# ECUv2.net
KiCad netlist of a schematic drawn in Altium Designer
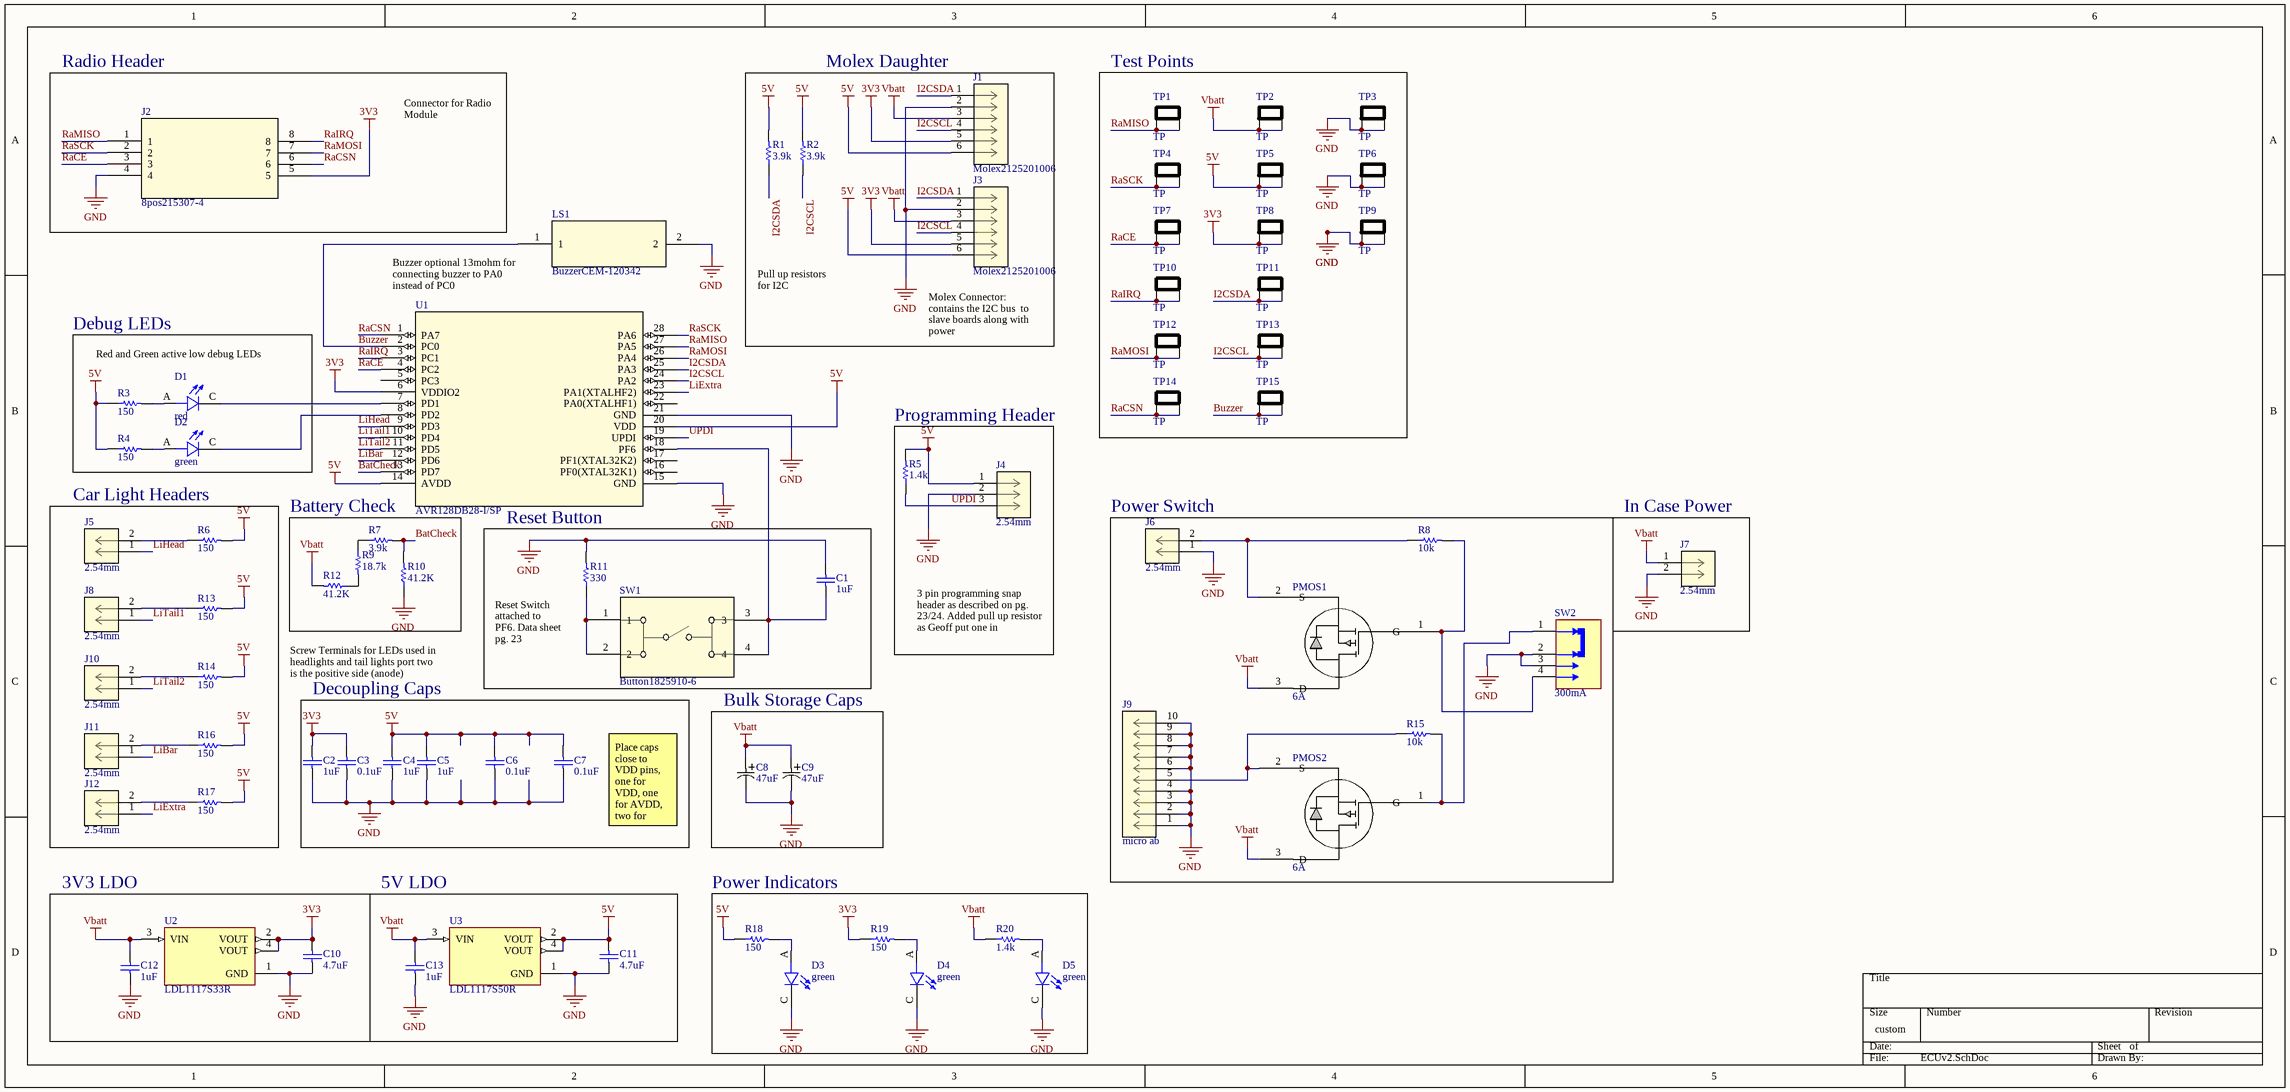
[diagram p0: ECUv2.SchDoc]

(export (version "E")
  (design (tool "Eeschema 10.0.6"))
  (components
    (comp (ref "C1")
      (value "1uF")
      (footprint "RES 0805")
      (fields
        (field (name "MANUFACTURER") "Samsung")
        (field (name "MANUFACTURER PART NUMBER") "CL21B105KBFNNNE")
      )
      (libsource (lib "Schlib1") (part "CAP CER 1uF 10% 50V 0805"))
    )
    (comp (ref "C2")
      (value "1uF")
      (footprint "RES 0805")
      (fields
        (field (name "MANUFACTURER") "Samsung")
        (field (name "MANUFACTURER PART NUMBER") "CL21B105KBFNNNE")
      )
      (libsource (lib "Schlib1") (part "CAP CER 1uF 10% 50V 0805"))
    )
    (comp (ref "C3")
      (value "0.1uF")
      (footprint "RES 0805")
      (fields
        (field (name "MANUFACTURER") "Yageo")
        (field (name "MANUFACTURER PART NUMBER") "CC0805KRX7R9BB104")
      )
      (libsource (lib "Schlib1") (part "CAP CER 0.1uF 10% 50V 0805"))
    )
    (comp (ref "C4")
      (value "1uF")
      (footprint "RES 0805")
      (fields
        (field (name "MANUFACTURER") "Samsung")
        (field (name "MANUFACTURER PART NUMBER") "CL21B105KBFNNNE")
      )
      (libsource (lib "Schlib1") (part "CAP CER 1uF 10% 50V 0805"))
    )
    (comp (ref "C5")
      (value "1uF")
      (footprint "RES 0805")
      (fields
        (field (name "MANUFACTURER") "Samsung")
        (field (name "MANUFACTURER PART NUMBER") "CL21B105KBFNNNE")
      )
      (libsource (lib "Schlib1") (part "CAP CER 1uF 10% 50V 0805"))
    )
    (comp (ref "C6")
      (value "0.1uF")
      (footprint "RES 0805")
      (fields
        (field (name "MANUFACTURER") "Yageo")
        (field (name "MANUFACTURER PART NUMBER") "CC0805KRX7R9BB104")
      )
      (libsource (lib "Schlib1") (part "CAP CER 0.1uF 10% 50V 0805"))
    )
    (comp (ref "C7")
      (value "0.1uF")
      (footprint "RES 0805")
      (fields
        (field (name "MANUFACTURER") "Yageo")
        (field (name "MANUFACTURER PART NUMBER") "CC0805KRX7R9BB104")
      )
      (libsource (lib "Schlib1") (part "CAP CER 0.1uF 10% 50V 0805"))
    )
    (comp (ref "C8")
      (value "47uF")
      (footprint "CAP ELC 47uF")
      (fields
        (field (name "MANUFACTURER") "Nichicon")
        (field (name "MANUFACTURER PART NUMBER") "UWT1H470MCL1GS")
      )
      (libsource (lib "Schlib1") (part "CAP ELCALUM 47uF 20% 50V"))
    )
    (comp (ref "C9")
      (value "47uF")
      (footprint "CAP ELC 47uF")
      (fields
        (field (name "MANUFACTURER") "Nichicon")
        (field (name "MANUFACTURER PART NUMBER") "UWT1H470MCL1GS")
      )
      (libsource (lib "Schlib1") (part "CAP ELCALUM 47uF 20% 50V"))
    )
    (comp (ref "C10")
      (value "4.7uF")
      (footprint "RES 0805")
      (fields
        (field (name "MANUFACTURER") "Samsung")
        (field (name "MANUFACTURER PART NUMBER") "CL21A475KAQNNNE")
      )
      (libsource (lib "Schlib1") (part "CAP CER 4.7uF 10% 25V 0805"))
    )
    (comp (ref "C11")
      (value "4.7uF")
      (footprint "RES 0805")
      (fields
        (field (name "MANUFACTURER") "Samsung")
        (field (name "MANUFACTURER PART NUMBER") "CL21A475KAQNNNE")
      )
      (libsource (lib "Schlib1") (part "CAP CER 4.7uF 10% 25V 0805"))
    )
    (comp (ref "C12")
      (value "1uF")
      (footprint "RES 0805")
      (fields
        (field (name "MANUFACTURER") "Samsung")
        (field (name "MANUFACTURER PART NUMBER") "CL21B105KBFNNNE")
      )
      (libsource (lib "Schlib1") (part "CAP CER 1uF 10% 50V 0805"))
    )
    (comp (ref "C13")
      (value "1uF")
      (footprint "RES 0805")
      (fields
        (field (name "MANUFACTURER") "Samsung")
        (field (name "MANUFACTURER PART NUMBER") "CL21B105KBFNNNE")
      )
      (libsource (lib "Schlib1") (part "CAP CER 1uF 10% 50V 0805"))
    )
    (comp (ref "D1")
      (value "red")
      (footprint "0603LED")
      (description "Single Color LED, Red, Diffused Milky White, 1.2mm")
      (fields (field (name "MANUFACTURER") "Rohm") (field (name "MANUFACTURER PART NUMBER") "SML-D12U1WT86"))
      (libsource (lib "Schlib1") (part "LED redSML-D12U1WT86"))
    )
    (comp (ref "D2")
      (value "green")
      (footprint "0603LED")
      (description "Single Color LED, Pure Green, Diffused Milky White, 1.2mm")
      (fields (field (name "MANUFACTURER") "Rohm") (field (name "MANUFACTURER PART NUMBER") "SML-D12P8WT86"))
      (libsource (lib "Schlib1") (part "LED greenSML-D12P8WT86"))
    )
    (comp (ref "D3")
      (value "green")
      (footprint "0603LED")
      (description "Single Color LED, Pure Green, Diffused Milky White, 1.2mm")
      (fields (field (name "MANUFACTURER") "Rohm") (field (name "MANUFACTURER PART NUMBER") "SML-D12P8WT86"))
      (libsource (lib "Schlib1") (part "LED greenSML-D12P8WT86"))
    )
    (comp (ref "D4")
      (value "green")
      (footprint "0603LED")
      (description "Single Color LED, Pure Green, Diffused Milky White, 1.2mm")
      (fields (field (name "MANUFACTURER") "Rohm") (field (name "MANUFACTURER PART NUMBER") "SML-D12P8WT86"))
      (libsource (lib "Schlib1") (part "LED greenSML-D12P8WT86"))
    )
    (comp (ref "D5")
      (value "green")
      (footprint "0603LED")
      (description "Single Color LED, Pure Green, Diffused Milky White, 1.2mm")
      (fields (field (name "MANUFACTURER") "Rohm") (field (name "MANUFACTURER PART NUMBER") "SML-D12P8WT86"))
      (libsource (lib "Schlib1") (part "LED greenSML-D12P8WT86"))
    )
    (comp (ref "J1")
      (value "Molex2125201006")
      (footprint "Molex2125201006")
      (description "Connector Power Header 6 Position 4.2mm Solder Through Hole Tray")
      (fields (field (name "MANUFACTURER") "Molex") (field (name "MANUFACTURER PART NUMBER") "212520-1006"))
      (libsource (lib "Schlib1") (part "Molex2125201006"))
    )
    (comp (ref "J2")
      (value "8pos215307-4")
      (footprint "215307-4")
      (fields
        (field (name "MANUFACTURER") "TE Connectivity")
        (field (name "MANUFACTURER PART NUMBER") "215307-4")
      )
      (libsource (lib "Schlib1") (part "8pos215307-4"))
    )
    (comp (ref "J3")
      (value "Molex2125201006")
      (footprint "Molex2125201006")
      (description "Connector Power Header 6 Position 4.2mm Solder Through Hole Tray")
      (fields (field (name "MANUFACTURER") "Molex") (field (name "MANUFACTURER PART NUMBER") "212520-1006"))
      (libsource (lib "Schlib1") (part "Molex2125201006"))
    )
    (comp (ref "J4")
      (value "2.54mm")
      (footprint "HEAD 2.54mm 3pos")
      (fields (field (name "MANUFACTURER") "Samtec") (field (name "MANUFACTURER PART NUMBER") "TS-103-T-A"))
      (libsource (lib "Schlib1") (part "HEAD 2.54mm 3pos"))
    )
    (comp (ref "J5")
      (value "2.54mm")
      (footprint "CON screw 2pos 2.54mm")
      (description "Barrier Strip Terminal Block, 6A, 1 Row(s), 1 Deck(s)")
      (fields
        (field (name "MANUFACTURER") "On-Shore Technology")
        (field (name "MANUFACTURER PART NUMBER") "OSTVN02A150")
        (field (name "SAFETY APPROVAL") "UL,CUL")
      )
      (libsource (lib "Schlib1") (part "CON screw 2pos 2.54mm"))
    )
    (comp (ref "J6")
      (value "2.54mm")
      (footprint "CON screw 2pos 2.54mm")
      (description "Barrier Strip Terminal Block, 6A, 1 Row(s), 1 Deck(s)")
      (fields
        (field (name "MANUFACTURER") "On-Shore Technology")
        (field (name "MANUFACTURER PART NUMBER") "OSTVN02A150")
        (field (name "SAFETY APPROVAL") "UL,CUL")
      )
      (libsource (lib "Schlib1") (part "CON screw 2pos 2.54mm"))
    )
    (comp (ref "J7")
      (value "2.54mm")
      (footprint "CON screw 2pos 2.54mm")
      (description "Barrier Strip Terminal Block, 6A, 1 Row(s), 1 Deck(s)")
      (fields
        (field (name "MANUFACTURER") "On-Shore Technology")
        (field (name "MANUFACTURER PART NUMBER") "OSTVN02A150")
        (field (name "SAFETY APPROVAL") "UL,CUL")
      )
      (libsource (lib "") (part "CON screw 2pos 2.54mm_1"))
    )
    (comp (ref "J8")
      (value "2.54mm")
      (footprint "CON screw 2pos 2.54mm")
      (description "Barrier Strip Terminal Block, 6A, 1 Row(s), 1 Deck(s)")
      (fields
        (field (name "MANUFACTURER") "On-Shore Technology")
        (field (name "MANUFACTURER PART NUMBER") "OSTVN02A150")
        (field (name "SAFETY APPROVAL") "UL,CUL")
      )
      (libsource (lib "Schlib1") (part "CON screw 2pos 2.54mm"))
    )
    (comp (ref "J9")
      (value "micro ab")
      (footprint "USB micro ab 0475900001")
      (description "USB Connector, 5 Contact(s), Female, Right Angle, Surface Mount Terminal, Locking, Receptacle")
      (fields (field (name "MANUFACTURER") "Molex") (field (name "MANUFACTURER PART NUMBER") "47590-0001"))
      (libsource (lib "Schlib1") (part "CON USB micro ab"))
    )
    (comp (ref "J10")
      (value "2.54mm")
      (footprint "CON screw 2pos 2.54mm")
      (description "Barrier Strip Terminal Block, 6A, 1 Row(s), 1 Deck(s)")
      (fields
        (field (name "MANUFACTURER") "On-Shore Technology")
        (field (name "MANUFACTURER PART NUMBER") "OSTVN02A150")
        (field (name "SAFETY APPROVAL") "UL,CUL")
      )
      (libsource (lib "Schlib1") (part "CON screw 2pos 2.54mm"))
    )
    (comp (ref "J11")
      (value "2.54mm")
      (footprint "CON screw 2pos 2.54mm")
      (description "Barrier Strip Terminal Block, 6A, 1 Row(s), 1 Deck(s)")
      (fields
        (field (name "MANUFACTURER") "On-Shore Technology")
        (field (name "MANUFACTURER PART NUMBER") "OSTVN02A150")
        (field (name "SAFETY APPROVAL") "UL,CUL")
      )
      (libsource (lib "Schlib1") (part "CON screw 2pos 2.54mm"))
    )
    (comp (ref "J12")
      (value "2.54mm")
      (footprint "CON screw 2pos 2.54mm")
      (description "Barrier Strip Terminal Block, 6A, 1 Row(s), 1 Deck(s)")
      (fields
        (field (name "MANUFACTURER") "On-Shore Technology")
        (field (name "MANUFACTURER PART NUMBER") "OSTVN02A150")
        (field (name "SAFETY APPROVAL") "UL,CUL")
      )
      (libsource (lib "Schlib1") (part "CON screw 2pos 2.54mm"))
    )
    (comp (ref "LS1")
      (value "BuzzerCEM-120342")
      (footprint "CEM-1203(42)")
      (description "Audio Signaling/Alarm Devices")
      (fields
        (field (name "MANUFACTURER") "CUI Devices")
        (field (name "MANUFACTURER PART NUMBER") "CEM-1203(42)")
      )
      (libsource (lib "Schlib1") (part "BuzzerCEM-120342"))
    )
    (comp (ref "PMOS1")
      (value "6A")
      (footprint "SOT-23F MOS PMOS 30V 6A")
      (fields
        (field (name "MANUFACTURER") "Toshiba")
        (field (name "MANUFACTURER PART NUMBER") "SSM3J372R,LF")
      )
      (libsource (lib "Schlib1") (part "MOS PMOS 30V 6A"))
    )
    (comp (ref "PMOS2")
      (value "6A")
      (footprint "SOT-23F MOS PMOS 30V 6A")
      (fields
        (field (name "MANUFACTURER") "Toshiba")
        (field (name "MANUFACTURER PART NUMBER") "SSM3J372R,LF")
      )
      (libsource (lib "Schlib1") (part "MOS PMOS 30V 6A"))
    )
    (comp (ref "R1")
      (value "3.9k")
      (footprint "RES 0805")
      (fields
        (field (name "MANUFACTURER") "Stackpole Electronics")
        (field (name "MANUFACTURER PART NUMBER") "RMCF0805FT3K92")
        (field (name "TOLERANCE") "1%")
      )
      (libsource (lib "Schlib1") (part "RES 3.9k 1% 0.125W 0805"))
    )
    (comp (ref "R2")
      (value "3.9k")
      (footprint "RES 0805")
      (fields
        (field (name "MANUFACTURER") "Stackpole Electronics")
        (field (name "MANUFACTURER PART NUMBER") "RMCF0805FT3K92")
        (field (name "TOLERANCE") "1%")
      )
      (libsource (lib "Schlib1") (part "RES 3.9k 1% 0.125W 0805"))
    )
    (comp (ref "R3")
      (value "150")
      (footprint "RES 0805")
      (fields
        (field (name "MANUFACTURER") "Yageo")
        (field (name "MANUFACTURER PART NUMBER") "RC0805FR-07150RL")
        (field (name "TOLERANCE") "1%")
      )
      (libsource (lib "Schlib1") (part "RES 150 1% 0.125 0805"))
    )
    (comp (ref "R4")
      (value "150")
      (footprint "RES 0805")
      (fields
        (field (name "MANUFACTURER") "Yageo")
        (field (name "MANUFACTURER PART NUMBER") "RC0805FR-07150RL")
        (field (name "TOLERANCE") "1%")
      )
      (libsource (lib "Schlib1") (part "RES 150 1% 0.125 0805"))
    )
    (comp (ref "R5")
      (value "1.4k")
      (footprint "RES 0805")
      (fields
        (field (name "MANUFACTURER") "Yageo")
        (field (name "MANUFACTURER PART NUMBER") "RC0805FR-071K4L")
        (field (name "TOLERANCE") "1%")
      )
      (libsource (lib "Schlib1") (part "RES 1.4k 1% 0.125W 0805"))
    )
    (comp (ref "R6")
      (value "150")
      (footprint "RES 0805")
      (fields
        (field (name "MANUFACTURER") "Yageo")
        (field (name "MANUFACTURER PART NUMBER") "RC0805FR-07150RL")
        (field (name "TOLERANCE") "1%")
      )
      (libsource (lib "Schlib1") (part "RES 150 1% 0.125 0805"))
    )
    (comp (ref "R7")
      (value "3.9k")
      (footprint "RES 0805")
      (fields
        (field (name "MANUFACTURER") "Stackpole Electronics")
        (field (name "MANUFACTURER PART NUMBER") "RMCF0805FT3K92")
        (field (name "TOLERANCE") "1%")
      )
      (libsource (lib "Schlib1") (part "RES 3.9k 1% 0.125W 0805"))
    )
    (comp (ref "R8")
      (value "10k")
      (footprint "RES 0805")
      (fields
        (field (name "MANUFACTURER") "Stackpole Electronics")
        (field (name "MANUFACTURER PART NUMBER") "RMCF0805FT10K0")
        (field (name "TOLERANCE") "1%")
      )
      (libsource (lib "Schlib1") (part "RES 10k 1% 0.125 0805"))
    )
    (comp (ref "R9")
      (value "18.7k")
      (footprint "RES 0805")
      (fields
        (field (name "MANUFACTURER") "Stackpole Electronics")
        (field (name "MANUFACTURER PART NUMBER") "RMCF0805FT18K7")
        (field (name "TOLERANCE") "1%")
      )
      (libsource (lib "Schlib1") (part "RES 18.7k 1% 0.125W 0805"))
    )
    (comp (ref "R10")
      (value "41.2K")
      (footprint "RES 0805")
      (fields
        (field (name "MANUFACTURER") "Vishay")
        (field (name "MANUFACTURER PART NUMBER") "CRCW080541K2FKEA")
        (field (name "TOLERANCE") "1%")
      )
      (libsource (lib "Schlib1") (part "RES 41.2K 1% 0.125W 0805"))
    )
    (comp (ref "R11")
      (value "330")
      (footprint "RES 0805")
      (fields
        (field (name "MANUFACTURER") "Stackpole Electronics")
        (field (name "MANUFACTURER PART NUMBER") "RMCF0805FT330R")
        (field (name "TOLERANCE") "1%")
      )
      (libsource (lib "Schlib1") (part "RES 330 1% 0.125W 0805"))
    )
    (comp (ref "R12")
      (value "41.2K")
      (footprint "RES 0805")
      (fields
        (field (name "MANUFACTURER") "Vishay")
        (field (name "MANUFACTURER PART NUMBER") "CRCW080541K2FKEA")
        (field (name "TOLERANCE") "1%")
      )
      (libsource (lib "Schlib1") (part "RES 41.2K 1% 0.125W 0805"))
    )
    (comp (ref "R13")
      (value "150")
      (footprint "RES 0805")
      (fields
        (field (name "MANUFACTURER") "Yageo")
        (field (name "MANUFACTURER PART NUMBER") "RC0805FR-07150RL")
        (field (name "TOLERANCE") "1%")
      )
      (libsource (lib "Schlib1") (part "RES 150 1% 0.125 0805"))
    )
    (comp (ref "R14")
      (value "150")
      (footprint "RES 0805")
      (fields
        (field (name "MANUFACTURER") "Yageo")
        (field (name "MANUFACTURER PART NUMBER") "RC0805FR-07150RL")
        (field (name "TOLERANCE") "1%")
      )
      (libsource (lib "Schlib1") (part "RES 150 1% 0.125 0805"))
    )
    (comp (ref "R15")
      (value "10k")
      (footprint "RES 0805")
      (fields
        (field (name "MANUFACTURER") "Stackpole Electronics")
        (field (name "MANUFACTURER PART NUMBER") "RMCF0805FT10K0")
        (field (name "TOLERANCE") "1%")
      )
      (libsource (lib "Schlib1") (part "RES 10k 1% 0.125 0805"))
    )
    (comp (ref "R16")
      (value "150")
      (footprint "RES 0805")
      (fields
        (field (name "MANUFACTURER") "Yageo")
        (field (name "MANUFACTURER PART NUMBER") "RC0805FR-07150RL")
        (field (name "TOLERANCE") "1%")
      )
      (libsource (lib "Schlib1") (part "RES 150 1% 0.125 0805"))
    )
    (comp (ref "R17")
      (value "150")
      (footprint "RES 0805")
      (fields
        (field (name "MANUFACTURER") "Yageo")
        (field (name "MANUFACTURER PART NUMBER") "RC0805FR-07150RL")
        (field (name "TOLERANCE") "1%")
      )
      (libsource (lib "Schlib1") (part "RES 150 1% 0.125 0805"))
    )
    (comp (ref "R18")
      (value "150")
      (footprint "RES 0805")
      (fields
        (field (name "MANUFACTURER") "Yageo")
        (field (name "MANUFACTURER PART NUMBER") "RC0805FR-07150RL")
        (field (name "TOLERANCE") "1%")
      )
      (libsource (lib "Schlib1") (part "RES 150 1% 0.125 0805"))
    )
    (comp (ref "R19")
      (value "150")
      (footprint "RES 0805")
      (fields
        (field (name "MANUFACTURER") "Yageo")
        (field (name "MANUFACTURER PART NUMBER") "RC0805FR-07150RL")
        (field (name "TOLERANCE") "1%")
      )
      (libsource (lib "Schlib1") (part "RES 150 1% 0.125 0805"))
    )
    (comp (ref "R20")
      (value "1.4k")
      (footprint "RES 0805")
      (fields
        (field (name "MANUFACTURER") "Yageo")
        (field (name "MANUFACTURER PART NUMBER") "RC0805FR-071K4L")
        (field (name "TOLERANCE") "1%")
      )
      (libsource (lib "Schlib1") (part "RES 1.4k 1% 0.125W 0805"))
    )
    (comp (ref "SW1")
      (value "Button1825910-6")
      (footprint "Button1825910-6")
      (fields
        (field (name "MANUFACTURER") "TE Connectivity Alcoswitch")
        (field (name "MANUFACTURER PART NUMBER") "1825910-6")
      )
      (libsource (lib "Schlib1") (part "Button1825910-6"))
    )
    (comp (ref "SW2")
      (value "300mA")
      (footprint "Switch On-On-On 300mA SLW-1277545-2A-RA-S-D")
      (description "12.7 x 7.5 x 4.5 mm, 2 mm Raised Slide Actuator, Right Angle, Through Hole, Slide Switch")
      (fields
        (field (name "MANUFACTURER") "Same Sky")
        (field (name "MANUFACTURER PART NUMBER") "SLW-1277545-2A-RA-S-D")
      )
      (libsource (lib "Schlib1") (part "SW On-On-On 300mA"))
    )
    (comp (ref "TP1")
      (value "TP")
      (footprint "RES 0805")
      (description "Testing/Accessories")
      (fields (field (name "MANUFACTURER") "KOA Speer") (field (name "MANUFACTURER PART NUMBER") "RCTCTE"))
      (libsource (lib "Schlib1") (part "TP clip 0805 RCTCTE"))
    )
    (comp (ref "TP2")
      (value "TP")
      (footprint "RES 0805")
      (description "Testing/Accessories")
      (fields (field (name "MANUFACTURER") "KOA Speer") (field (name "MANUFACTURER PART NUMBER") "RCTCTE"))
      (libsource (lib "Schlib1") (part "TP clip 0805 RCTCTE"))
    )
    (comp (ref "TP3")
      (value "TP")
      (footprint "RES 0805")
      (description "Testing/Accessories")
      (fields (field (name "MANUFACTURER") "KOA Speer") (field (name "MANUFACTURER PART NUMBER") "RCTCTE"))
      (libsource (lib "Schlib1") (part "TP clip 0805 RCTCTE"))
    )
    (comp (ref "TP4")
      (value "TP")
      (footprint "RES 0805")
      (description "Testing/Accessories")
      (fields (field (name "MANUFACTURER") "KOA Speer") (field (name "MANUFACTURER PART NUMBER") "RCTCTE"))
      (libsource (lib "Schlib1") (part "TP clip 0805 RCTCTE"))
    )
    (comp (ref "TP5")
      (value "TP")
      (footprint "RES 0805")
      (description "Testing/Accessories")
      (fields (field (name "MANUFACTURER") "KOA Speer") (field (name "MANUFACTURER PART NUMBER") "RCTCTE"))
      (libsource (lib "Schlib1") (part "TP clip 0805 RCTCTE"))
    )
    (comp (ref "TP6")
      (value "TP")
      (footprint "RES 0805")
      (description "Testing/Accessories")
      (fields (field (name "MANUFACTURER") "KOA Speer") (field (name "MANUFACTURER PART NUMBER") "RCTCTE"))
      (libsource (lib "Schlib1") (part "TP clip 0805 RCTCTE"))
    )
    (comp (ref "TP7")
      (value "TP")
      (footprint "RES 0805")
      (description "Testing/Accessories")
      (fields (field (name "MANUFACTURER") "KOA Speer") (field (name "MANUFACTURER PART NUMBER") "RCTCTE"))
      (libsource (lib "Schlib1") (part "TP clip 0805 RCTCTE"))
    )
    (comp (ref "TP8")
      (value "TP")
      (footprint "RES 0805")
      (description "Testing/Accessories")
      (fields (field (name "MANUFACTURER") "KOA Speer") (field (name "MANUFACTURER PART NUMBER") "RCTCTE"))
      (libsource (lib "Schlib1") (part "TP clip 0805 RCTCTE"))
    )
    (comp (ref "TP9")
      (value "TP")
      (footprint "RES 0805")
      (description "Testing/Accessories")
      (fields (field (name "MANUFACTURER") "KOA Speer") (field (name "MANUFACTURER PART NUMBER") "RCTCTE"))
      (libsource (lib "Schlib1") (part "TP clip 0805 RCTCTE"))
    )
    (comp (ref "TP10")
      (value "TP")
      (footprint "RES 0805")
      (description "Testing/Accessories")
      (fields (field (name "MANUFACTURER") "KOA Speer") (field (name "MANUFACTURER PART NUMBER") "RCTCTE"))
      (libsource (lib "Schlib1") (part "TP clip 0805 RCTCTE"))
    )
    (comp (ref "TP11")
      (value "TP")
      (footprint "RES 0805")
      (description "Testing/Accessories")
      (fields (field (name "MANUFACTURER") "KOA Speer") (field (name "MANUFACTURER PART NUMBER") "RCTCTE"))
      (libsource (lib "Schlib1") (part "TP clip 0805 RCTCTE"))
    )
    (comp (ref "TP12")
      (value "TP")
      (footprint "RES 0805")
      (description "Testing/Accessories")
      (fields (field (name "MANUFACTURER") "KOA Speer") (field (name "MANUFACTURER PART NUMBER") "RCTCTE"))
      (libsource (lib "Schlib1") (part "TP clip 0805 RCTCTE"))
    )
    (comp (ref "TP13")
      (value "TP")
      (footprint "RES 0805")
      (description "Testing/Accessories")
      (fields (field (name "MANUFACTURER") "KOA Speer") (field (name "MANUFACTURER PART NUMBER") "RCTCTE"))
      (libsource (lib "Schlib1") (part "TP clip 0805 RCTCTE"))
    )
    (comp (ref "TP14")
      (value "TP")
      (footprint "RES 0805")
      (description "Testing/Accessories")
      (fields (field (name "MANUFACTURER") "KOA Speer") (field (name "MANUFACTURER PART NUMBER") "RCTCTE"))
      (libsource (lib "Schlib1") (part "TP clip 0805 RCTCTE"))
    )
    (comp (ref "TP15")
      (value "TP")
      (footprint "RES 0805")
      (description "Testing/Accessories")
      (fields (field (name "MANUFACTURER") "KOA Speer") (field (name "MANUFACTURER PART NUMBER") "RCTCTE"))
      (libsource (lib "Schlib1") (part "TP clip 0805 RCTCTE"))
    )
    (comp (ref "U1")
      (value "AVR128DB28-I/SP")
      (footprint "AVR128DB28-ISP")
      (description "RISC Microcontroller, 8-Bit, FLASH, AVR CPU, 24MHz, CMOS, PDIP28")
      (fields (field (name "MANUFACTURER") "Microchip"))
      (libsource (lib "Schlib1") (part "AVR128DB28-I/SP"))
    )
    (comp (ref "U2")
      (value "LDL1117S33R")
      (footprint "SOT230P700X180-4N")
      (description "Fixed Positive LDO Regulator, 3.3V, 0.6V Dropout, PDSO4")
      (fields (field (name "MANUFACTURER") "STMicroelectronics"))
      (libsource (lib "Schlib1") (part "LDL1117S33R"))
    )
    (comp (ref "U3")
      (value "LDL1117S50R")
      (footprint "SOT230P700X180-4N")
      (description "Fixed Positive LDO Regulator, 5V, 0.6V Dropout, PDSO4")
      (fields (field (name "MANUFACTURER") "STMicroelectronics"))
      (libsource (lib "Schlib1") (part "LDL1117S50R"))
    )
  )
  (nets
    (net (code "1") (name "/BatCheck") (class "Default")
      (node (ref "R10") (pin "2") (pinfunction "2_2") (pintype "passive"))
      (node (ref "R7") (pin "2") (pinfunction "2_2") (pintype "passive"))
      (node (ref "U1") (pin "13") (pinfunction "PD7_13") (pintype "bidirectional"))
    )
    (net (code "2") (name "/Buzzer") (class "Default")
      (node (ref "LS1") (pin "1") (pinfunction "1_1") (pintype "passive"))
      (node (ref "TP15") (pin "1") (pinfunction "1_1") (pintype "passive"))
      (node (ref "TP15") (pin "2") (pinfunction "2_2") (pintype "passive"))
      (node (ref "U1") (pin "2") (pinfunction "PC0_2") (pintype "bidirectional"))
    )
    (net (code "3") (name "/I2CSCL") (class "Default")
      (node (ref "J1") (pin "4") (pinfunction "4_4") (pintype "passive"))
      (node (ref "J3") (pin "4") (pinfunction "4_4") (pintype "passive"))
      (node (ref "R2") (pin "1") (pinfunction "1_1") (pintype "passive"))
      (node (ref "TP13") (pin "1") (pinfunction "1_1") (pintype "passive"))
      (node (ref "TP13") (pin "2") (pinfunction "2_2") (pintype "passive"))
      (node (ref "U1") (pin "24") (pinfunction "PA2_24") (pintype "bidirectional"))
    )
    (net (code "4") (name "/I2CSDA") (class "Default")
      (node (ref "J1") (pin "1") (pinfunction "1_1") (pintype "passive"))
      (node (ref "J3") (pin "1") (pinfunction "1_1") (pintype "passive"))
      (node (ref "R1") (pin "1") (pinfunction "1_1") (pintype "passive"))
      (node (ref "TP11") (pin "1") (pinfunction "1_1") (pintype "passive"))
      (node (ref "TP11") (pin "2") (pinfunction "2_2") (pintype "passive"))
      (node (ref "U1") (pin "25") (pinfunction "PA3_25") (pintype "bidirectional"))
    )
    (net (code "5") (name "/LiBar") (class "Default")
      (node (ref "J11") (pin "1") (pinfunction "1_1") (pintype "passive"))
      (node (ref "U1") (pin "12") (pinfunction "PD6_12") (pintype "bidirectional"))
    )
    (net (code "6") (name "/LiExtra") (class "Default")
      (node (ref "J12") (pin "1") (pinfunction "1_1") (pintype "passive"))
      (node (ref "U1") (pin "23") (pinfunction "PA1(XTALHF2)_23") (pintype "bidirectional"))
    )
    (net (code "7") (name "/LiHead") (class "Default")
      (node (ref "J5") (pin "1") (pinfunction "1_1") (pintype "passive"))
      (node (ref "U1") (pin "9") (pinfunction "PD3_9") (pintype "bidirectional"))
    )
    (net (code "8") (name "/LiTail1") (class "Default")
      (node (ref "J8") (pin "1") (pinfunction "1_1") (pintype "passive"))
      (node (ref "U1") (pin "10") (pinfunction "PD4_10") (pintype "bidirectional"))
    )
    (net (code "9") (name "/LiTail2") (class "Default")
      (node (ref "J10") (pin "1") (pinfunction "1_1") (pintype "passive"))
      (node (ref "U1") (pin "11") (pinfunction "PD5_11") (pintype "bidirectional"))
    )
    (net (code "10") (name "/RaCE") (class "Default")
      (node (ref "J2") (pin "3") (pinfunction "3_3") (pintype "passive"))
      (node (ref "TP7") (pin "1") (pinfunction "1_1") (pintype "passive"))
      (node (ref "TP7") (pin "2") (pinfunction "2_2") (pintype "passive"))
      (node (ref "U1") (pin "4") (pinfunction "PC2_4") (pintype "bidirectional"))
    )
    (net (code "11") (name "/RaCSN") (class "Default")
      (node (ref "J2") (pin "6") (pinfunction "6_6") (pintype "passive"))
      (node (ref "TP14") (pin "1") (pinfunction "1_1") (pintype "passive"))
      (node (ref "TP14") (pin "2") (pinfunction "2_2") (pintype "passive"))
      (node (ref "U1") (pin "1") (pinfunction "PA7_1") (pintype "bidirectional"))
    )
    (net (code "12") (name "/RaIRQ") (class "Default")
      (node (ref "J2") (pin "8") (pinfunction "8_8") (pintype "passive"))
      (node (ref "TP10") (pin "1") (pinfunction "1_1") (pintype "passive"))
      (node (ref "TP10") (pin "2") (pinfunction "2_2") (pintype "passive"))
      (node (ref "U1") (pin "3") (pinfunction "PC1_3") (pintype "bidirectional"))
    )
    (net (code "13") (name "/RaMISO") (class "Default")
      (node (ref "J2") (pin "1") (pinfunction "1_1") (pintype "passive"))
      (node (ref "TP1") (pin "1") (pinfunction "1_1") (pintype "passive"))
      (node (ref "TP1") (pin "2") (pinfunction "2_2") (pintype "passive"))
      (node (ref "U1") (pin "27") (pinfunction "PA5_27") (pintype "bidirectional"))
    )
    (net (code "14") (name "/RaMOSI") (class "Default")
      (node (ref "J2") (pin "7") (pinfunction "7_7") (pintype "passive"))
      (node (ref "TP12") (pin "1") (pinfunction "1_1") (pintype "passive"))
      (node (ref "TP12") (pin "2") (pinfunction "2_2") (pintype "passive"))
      (node (ref "U1") (pin "26") (pinfunction "PA4_26") (pintype "bidirectional"))
    )
    (net (code "15") (name "/RaSCK") (class "Default")
      (node (ref "J2") (pin "2") (pinfunction "2_2") (pintype "passive"))
      (node (ref "TP4") (pin "1") (pinfunction "1_1") (pintype "passive"))
      (node (ref "TP4") (pin "2") (pinfunction "2_2") (pintype "passive"))
      (node (ref "U1") (pin "28") (pinfunction "PA6_28") (pintype "bidirectional"))
    )
    (net (code "16") (name "/UPDI") (class "Default")
      (node (ref "J4") (pin "3") (pinfunction "3_3") (pintype "passive"))
      (node (ref "R5") (pin "1") (pinfunction "1_1") (pintype "passive"))
      (node (ref "U1") (pin "19") (pinfunction "UPDI_19") (pintype "bidirectional"))
    )
    (net (code "17") (name "3V3") (class "Default")
      (node (ref "C10") (pin "2") (pinfunction "2_2") (pintype "passive"))
      (node (ref "C2") (pin "2") (pinfunction "2_2") (pintype "passive"))
      (node (ref "C3") (pin "2") (pinfunction "2_2") (pintype "passive"))
      (node (ref "J1") (pin "5") (pinfunction "5_5") (pintype "passive"))
      (node (ref "J2") (pin "5") (pinfunction "5_5") (pintype "passive"))
      (node (ref "J3") (pin "5") (pinfunction "5_5") (pintype "passive"))
      (node (ref "R19") (pin "1") (pinfunction "1_1") (pintype "passive"))
      (node (ref "TP8") (pin "1") (pinfunction "1_1") (pintype "passive"))
      (node (ref "TP8") (pin "2") (pinfunction "2_2") (pintype "passive"))
      (node (ref "U1") (pin "6") (pinfunction "VDDIO2_6") (pintype "power_in"))
      (node (ref "U2") (pin "2") (pinfunction "VOUT_2") (pintype "output"))
      (node (ref "U2") (pin "4") (pinfunction "VOUT_4") (pintype "output"))
    )
    (net (code "18") (name "5V") (class "Default")
      (node (ref "C11") (pin "2") (pinfunction "2_2") (pintype "passive"))
      (node (ref "C4") (pin "2") (pinfunction "2_2") (pintype "passive"))
      (node (ref "C5") (pin "1") (pinfunction "1_1") (pintype "passive"))
      (node (ref "C6") (pin "2") (pinfunction "2_2") (pintype "passive"))
      (node (ref "C7") (pin "2") (pinfunction "2_2") (pintype "passive"))
      (node (ref "J1") (pin "6") (pinfunction "6_6") (pintype "passive"))
      (node (ref "J3") (pin "6") (pinfunction "6_6") (pintype "passive"))
      (node (ref "J4") (pin "1") (pinfunction "1_1") (pintype "passive"))
      (node (ref "R1") (pin "2") (pinfunction "2_2") (pintype "passive"))
      (node (ref "R13") (pin "2") (pinfunction "2_2") (pintype "passive"))
      (node (ref "R14") (pin "2") (pinfunction "2_2") (pintype "passive"))
      (node (ref "R16") (pin "2") (pinfunction "2_2") (pintype "passive"))
      (node (ref "R17") (pin "2") (pinfunction "2_2") (pintype "passive"))
      (node (ref "R18") (pin "1") (pinfunction "1_1") (pintype "passive"))
      (node (ref "R2") (pin "2") (pinfunction "2_2") (pintype "passive"))
      (node (ref "R3") (pin "1") (pinfunction "1_1") (pintype "passive"))
      (node (ref "R4") (pin "1") (pinfunction "1_1") (pintype "passive"))
      (node (ref "R5") (pin "2") (pinfunction "2_2") (pintype "passive"))
      (node (ref "R6") (pin "2") (pinfunction "2_2") (pintype "passive"))
      (node (ref "TP5") (pin "1") (pinfunction "1_1") (pintype "passive"))
      (node (ref "TP5") (pin "2") (pinfunction "2_2") (pintype "passive"))
      (node (ref "U1") (pin "14") (pinfunction "AVDD_14") (pintype "power_in"))
      (node (ref "U1") (pin "20") (pinfunction "VDD_20") (pintype "power_in"))
      (node (ref "U3") (pin "2") (pinfunction "VOUT_2") (pintype "output"))
      (node (ref "U3") (pin "4") (pinfunction "VOUT_4") (pintype "output"))
    )
    (net (code "19") (name "GND") (class "Default")
      (node (ref "C1") (pin "2") (pinfunction "2_2") (pintype "passive"))
      (node (ref "C10") (pin "1") (pinfunction "1_1") (pintype "passive"))
      (node (ref "C11") (pin "1") (pinfunction "1_1") (pintype "passive"))
      (node (ref "C12") (pin "1") (pinfunction "1_1") (pintype "passive"))
      (node (ref "C13") (pin "1") (pinfunction "1_1") (pintype "passive"))
      (node (ref "C2") (pin "1") (pinfunction "1_1") (pintype "passive"))
      (node (ref "C3") (pin "1") (pinfunction "1_1") (pintype "passive"))
      (node (ref "C4") (pin "1") (pinfunction "1_1") (pintype "passive"))
      (node (ref "C5") (pin "2") (pinfunction "2_2") (pintype "passive"))
      (node (ref "C6") (pin "1") (pinfunction "1_1") (pintype "passive"))
      (node (ref "C7") (pin "1") (pinfunction "1_1") (pintype "passive"))
      (node (ref "C8") (pin "2") (pinfunction "2_2") (pintype "passive"))
      (node (ref "C9") (pin "2") (pinfunction "2_2") (pintype "passive"))
      (node (ref "D3") (pin "C") (pinfunction "C_C") (pintype "passive"))
      (node (ref "D4") (pin "C") (pinfunction "C_C") (pintype "passive"))
      (node (ref "D5") (pin "C") (pinfunction "C_C") (pintype "passive"))
      (node (ref "J1") (pin "2") (pinfunction "2_2") (pintype "passive"))
      (node (ref "J2") (pin "4") (pinfunction "4_4") (pintype "passive"))
      (node (ref "J3") (pin "2") (pinfunction "2_2") (pintype "passive"))
      (node (ref "J4") (pin "2") (pinfunction "2_2") (pintype "passive"))
      (node (ref "J6") (pin "1") (pinfunction "1_1") (pintype "passive"))
      (node (ref "J7") (pin "2") (pinfunction "2_2") (pintype "passive"))
      (node (ref "J9") (pin "1") (pinfunction "VBUS_1") (pintype "passive"))
      (node (ref "J9") (pin "10") (pinfunction "SHIELD_10") (pintype "power_in"))
      (node (ref "J9") (pin "2") (pinfunction "D-_2") (pintype "passive"))
      (node (ref "J9") (pin "3") (pinfunction "D+_3") (pintype "passive"))
      (node (ref "J9") (pin "4") (pinfunction "ID_4") (pintype "passive"))
      (node (ref "J9") (pin "6") (pinfunction "SHIELD_6") (pintype "power_in"))
      (node (ref "J9") (pin "7") (pinfunction "SHIELD_7") (pintype "power_in"))
      (node (ref "J9") (pin "8") (pinfunction "SHIELD_8") (pintype "power_in"))
      (node (ref "J9") (pin "9") (pinfunction "SHIELD_9") (pintype "power_in"))
      (node (ref "LS1") (pin "2") (pinfunction "2_2") (pintype "passive"))
      (node (ref "R10") (pin "1") (pinfunction "1_1") (pintype "passive"))
      (node (ref "R11") (pin "2") (pinfunction "2_2") (pintype "passive"))
      (node (ref "SW2") (pin "2") (pinfunction "2_2") (pintype "passive"))
      (node (ref "SW2") (pin "3") (pinfunction "3_3") (pintype "passive"))
      (node (ref "TP3") (pin "1") (pinfunction "1_1") (pintype "passive"))
      (node (ref "TP3") (pin "2") (pinfunction "2_2") (pintype "passive"))
      (node (ref "TP6") (pin "1") (pinfunction "1_1") (pintype "passive"))
      (node (ref "TP6") (pin "2") (pinfunction "2_2") (pintype "passive"))
      (node (ref "TP9") (pin "1") (pinfunction "1_1") (pintype "passive"))
      (node (ref "TP9") (pin "2") (pinfunction "2_2") (pintype "passive"))
      (node (ref "U1") (pin "15") (pinfunction "GND_15") (pintype "power_in"))
      (node (ref "U1") (pin "21") (pinfunction "GND_21") (pintype "power_in"))
      (node (ref "U2") (pin "1") (pinfunction "GND_1") (pintype "power_in"))
      (node (ref "U3") (pin "1") (pinfunction "GND_1") (pintype "power_in"))
    )
    (net (code "20") (name "Net-(D1-PadA)") (class "Default")
      (node (ref "D1") (pin "A") (pinfunction "A_A") (pintype "passive"))
      (node (ref "R3") (pin "2") (pinfunction "2_2") (pintype "passive"))
    )
    (net (code "21") (name "Net-(D2-PadA)") (class "Default")
      (node (ref "D2") (pin "A") (pinfunction "A_A") (pintype "passive"))
      (node (ref "R4") (pin "2") (pinfunction "2_2") (pintype "passive"))
    )
    (net (code "22") (name "Net-(D3-PadA)") (class "Default")
      (node (ref "D3") (pin "A") (pinfunction "A_A") (pintype "passive"))
      (node (ref "R18") (pin "2") (pinfunction "2_2") (pintype "passive"))
    )
    (net (code "23") (name "Net-(D4-PadA)") (class "Default")
      (node (ref "D4") (pin "A") (pinfunction "A_A") (pintype "passive"))
      (node (ref "R19") (pin "2") (pinfunction "2_2") (pintype "passive"))
    )
    (net (code "24") (name "Net-(D5-PadA)") (class "Default")
      (node (ref "D5") (pin "A") (pinfunction "A_A") (pintype "passive"))
      (node (ref "R20") (pin "2") (pinfunction "2_2") (pintype "passive"))
    )
    (net (code "25") (name "Net-(J5-Pad2)") (class "Default")
      (node (ref "J5") (pin "2") (pinfunction "2_2") (pintype "passive"))
      (node (ref "R6") (pin "1") (pinfunction "1_1") (pintype "passive"))
    )
    (net (code "26") (name "Net-(J8-Pad2)") (class "Default")
      (node (ref "J8") (pin "2") (pinfunction "2_2") (pintype "passive"))
      (node (ref "R13") (pin "1") (pinfunction "1_1") (pintype "passive"))
    )
    (net (code "27") (name "Net-(J9-GND)") (class "Default")
      (node (ref "J9") (pin "5") (pinfunction "GND_5") (pintype "power_in"))
      (node (ref "PMOS2") (pin "2") (pinfunction "S_2") (pintype "passive"))
      (node (ref "R15") (pin "1") (pinfunction "1_1") (pintype "passive"))
    )
    (net (code "28") (name "Net-(J10-Pad2)") (class "Default")
      (node (ref "J10") (pin "2") (pinfunction "2_2") (pintype "passive"))
      (node (ref "R14") (pin "1") (pinfunction "1_1") (pintype "passive"))
    )
    (net (code "29") (name "Net-(J11-Pad2)") (class "Default")
      (node (ref "J11") (pin "2") (pinfunction "2_2") (pintype "passive"))
      (node (ref "R16") (pin "1") (pinfunction "1_1") (pintype "passive"))
    )
    (net (code "30") (name "Net-(J12-Pad2)") (class "Default")
      (node (ref "J12") (pin "2") (pinfunction "2_2") (pintype "passive"))
      (node (ref "R17") (pin "1") (pinfunction "1_1") (pintype "passive"))
    )
    (net (code "31") (name "Net-(PMOS1-G)") (class "Default")
      (node (ref "PMOS1") (pin "1") (pinfunction "G_1") (pintype "passive"))
      (node (ref "R8") (pin "2") (pinfunction "2_2") (pintype "passive"))
      (node (ref "SW2") (pin "4") (pinfunction "4_4") (pintype "passive"))
    )
    (net (code "32") (name "Net-(PMOS1-S)") (class "Default")
      (node (ref "J6") (pin "2") (pinfunction "2_2") (pintype "passive"))
      (node (ref "PMOS1") (pin "2") (pinfunction "S_2") (pintype "passive"))
      (node (ref "R8") (pin "1") (pinfunction "1_1") (pintype "passive"))
    )
    (net (code "33") (name "Net-(PMOS2-G)") (class "Default")
      (node (ref "PMOS2") (pin "1") (pinfunction "G_1") (pintype "passive"))
      (node (ref "R15") (pin "2") (pinfunction "2_2") (pintype "passive"))
      (node (ref "SW2") (pin "1") (pinfunction "1_1") (pintype "passive"))
    )
    (net (code "34") (name "Net-(R7-Pad1)") (class "Default")
      (node (ref "R7") (pin "1") (pinfunction "1_1") (pintype "passive"))
      (node (ref "R9") (pin "1") (pinfunction "1_1") (pintype "passive"))
    )
    (net (code "35") (name "Net-(R11-Pad1)") (class "Default")
      (node (ref "R11") (pin "1") (pinfunction "1_1") (pintype "passive"))
      (node (ref "SW1") (pin "1") (pinfunction "1_1") (pintype "passive"))
      (node (ref "SW1") (pin "2") (pinfunction "2_2") (pintype "passive"))
    )
    (net (code "36") (name "Net-(R12-Pad1)") (class "Default")
      (node (ref "R12") (pin "1") (pinfunction "1_1") (pintype "passive"))
      (node (ref "R9") (pin "2") (pinfunction "2_2") (pintype "passive"))
    )
    (net (code "37") (name "Net-(U1-PD1)") (class "Default")
      (node (ref "D1") (pin "C") (pinfunction "C_C") (pintype "passive"))
      (node (ref "U1") (pin "7") (pinfunction "PD1_7") (pintype "bidirectional"))
    )
    (net (code "38") (name "Net-(U1-PD2)") (class "Default")
      (node (ref "D2") (pin "C") (pinfunction "C_C") (pintype "passive"))
      (node (ref "U1") (pin "8") (pinfunction "PD2_8") (pintype "bidirectional"))
    )
    (net (code "39") (name "Net-(U1-PF6)") (class "Default")
      (node (ref "C1") (pin "1") (pinfunction "1_1") (pintype "passive"))
      (node (ref "SW1") (pin "3") (pinfunction "3_3") (pintype "passive"))
      (node (ref "SW1") (pin "4") (pinfunction "4_4") (pintype "passive"))
      (node (ref "U1") (pin "18") (pinfunction "PF6_18") (pintype "bidirectional"))
    )
    (net (code "40") (name "Vbatt") (class "Default")
      (node (ref "C12") (pin "2") (pinfunction "2_2") (pintype "passive"))
      (node (ref "C13") (pin "2") (pinfunction "2_2") (pintype "passive"))
      (node (ref "C8") (pin "1") (pinfunction "1_1") (pintype "passive"))
      (node (ref "C9") (pin "1") (pinfunction "1_1") (pintype "passive"))
      (node (ref "J1") (pin "3") (pinfunction "3_3") (pintype "passive"))
      (node (ref "J3") (pin "3") (pinfunction "3_3") (pintype "passive"))
      (node (ref "J7") (pin "1") (pinfunction "1_1") (pintype "passive"))
      (node (ref "PMOS1") (pin "3") (pinfunction "D_3") (pintype "passive"))
      (node (ref "PMOS2") (pin "3") (pinfunction "D_3") (pintype "passive"))
      (node (ref "R12") (pin "2") (pinfunction "2_2") (pintype "passive"))
      (node (ref "R20") (pin "1") (pinfunction "1_1") (pintype "passive"))
      (node (ref "TP2") (pin "1") (pinfunction "1_1") (pintype "passive"))
      (node (ref "TP2") (pin "2") (pinfunction "2_2") (pintype "passive"))
      (node (ref "U2") (pin "3") (pinfunction "VIN_3") (pintype "input"))
      (node (ref "U3") (pin "3") (pinfunction "VIN_3") (pintype "input"))
    )
    (net (code "41") (name "unconnected-(U1-PA0(XTALHF1)-Pad22)") (class "Default")
      (node (ref "U1") (pin "22") (pinfunction "PA0(XTALHF1)_22") (pintype "bidirectional"))
    )
    (net (code "42") (name "unconnected-(U1-PC3-Pad5)") (class "Default")
      (node (ref "U1") (pin "5") (pinfunction "PC3_5") (pintype "bidirectional"))
    )
    (net (code "43") (name "unconnected-(U1-PF0(XTAL32K1)-Pad16)") (class "Default")
      (node (ref "U1") (pin "16") (pinfunction "PF0(XTAL32K1)_16") (pintype "bidirectional"))
    )
    (net (code "44") (name "unconnected-(U1-PF1(XTAL32K2)-Pad17)") (class "Default")
      (node (ref "U1") (pin "17") (pinfunction "PF1(XTAL32K2)_17") (pintype "bidirectional"))
    )
  )
)
